# mrShark_Debugger.net
KiCad netlist of a schematic drawn in EAGLE
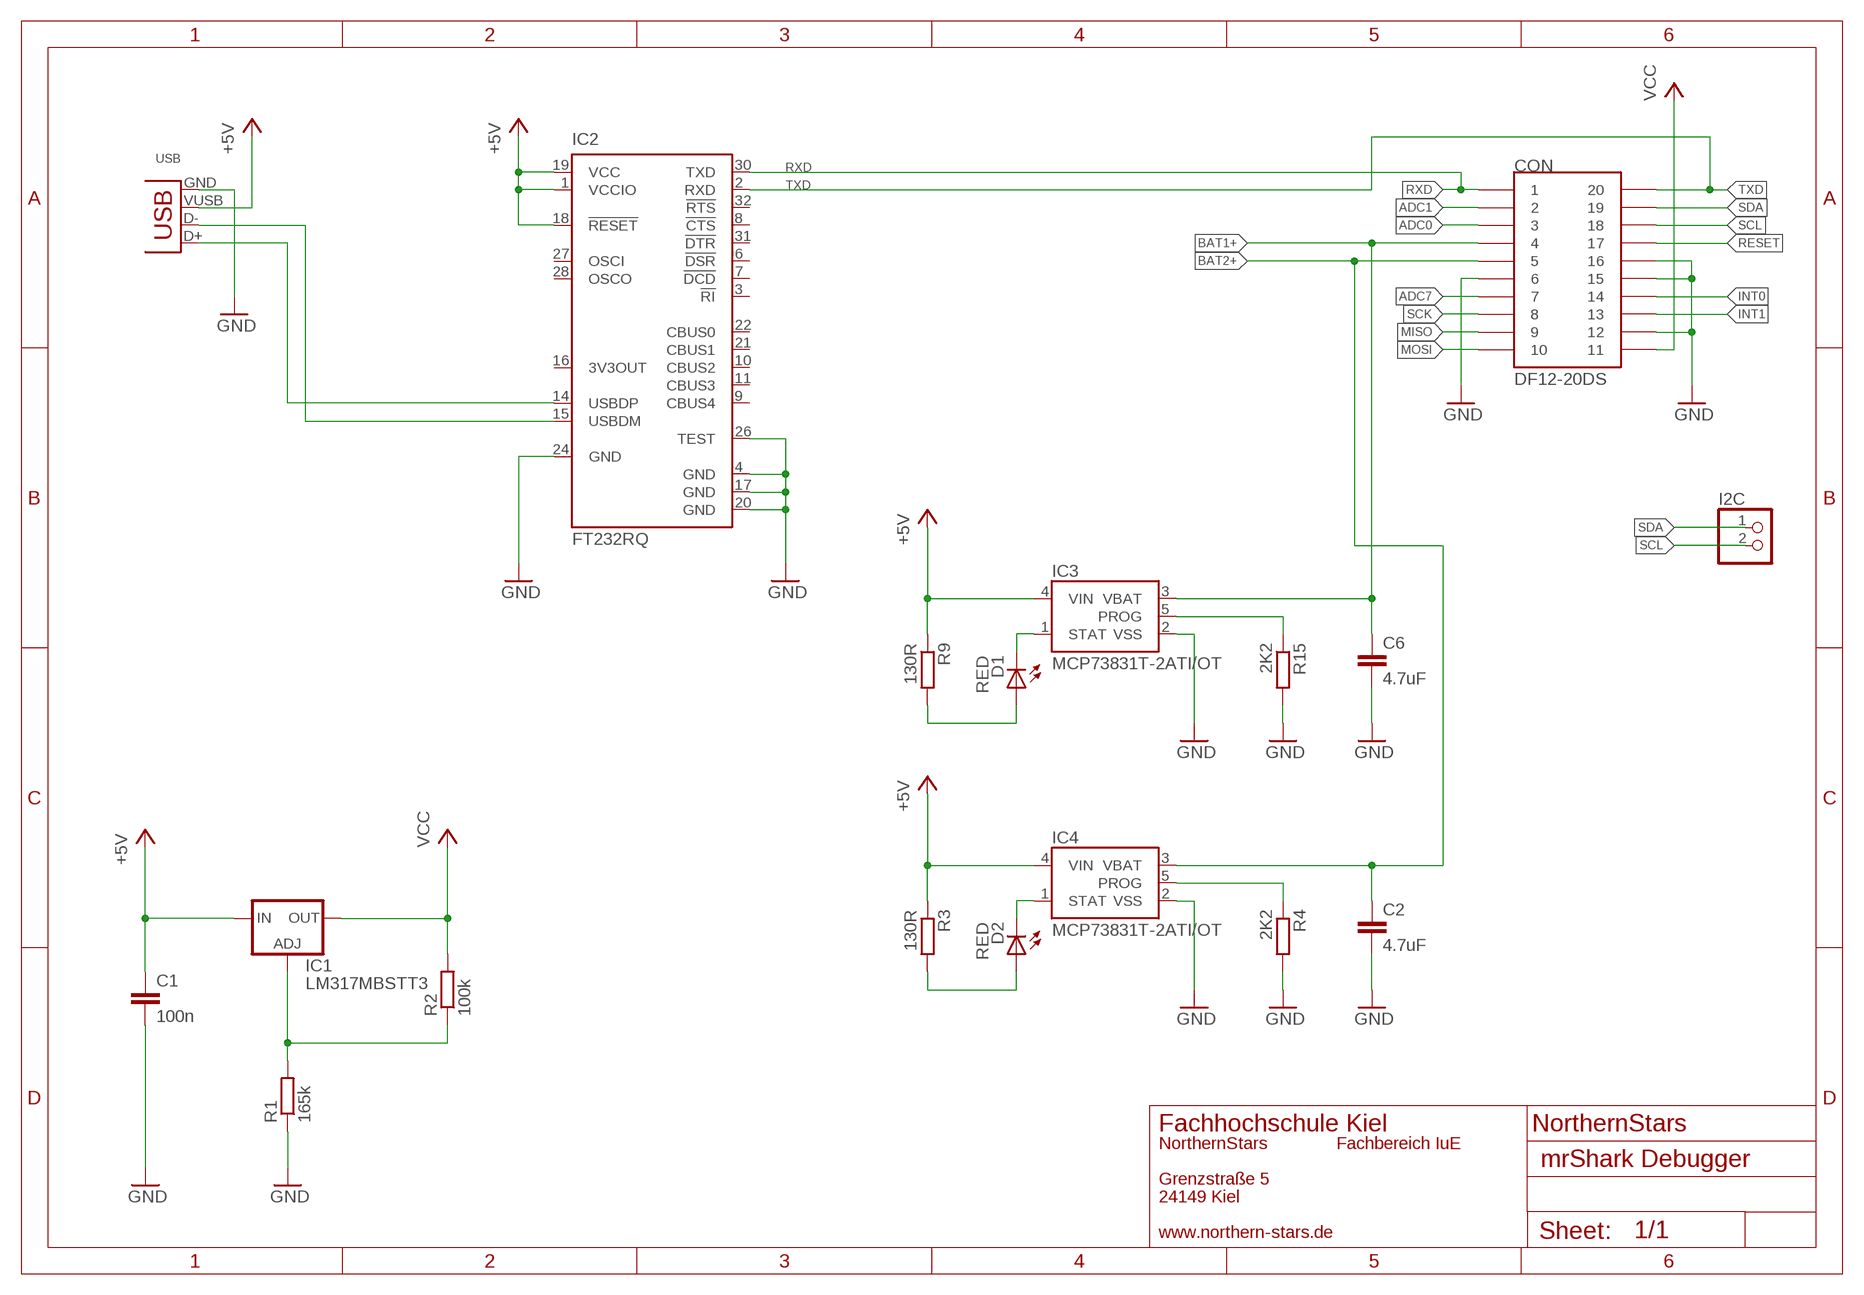
[diagram p0: schematic, sheet 1]

(export (version "E")
  (design (tool "Eeschema 10.0.6"))
  (components
    (comp (ref "C1")
      (value "100n")
      (footprint "eagle-import:C0201")
      (libsource (lib "eagle-import") (part "C-EUC0201"))
    )
    (comp (ref "C2")
      (value "4.7uF")
      (footprint "eagle-import:C0805")
      (libsource (lib "eagle-import") (part "C-EUC0805"))
    )
    (comp (ref "C6")
      (value "4.7uF")
      (footprint "eagle-import:C0805")
      (libsource (lib "eagle-import") (part "C-EUC0805"))
    )
    (comp (ref "CON")
      (value "DF12-20DS")
      (footprint "eagle-import:DF12-20DS")
      (libsource (lib "eagle-import") (part "DF12-20DS"))
    )
    (comp (ref "D1")
      (value "RED")
      (footprint "eagle-import:CHIP-LED0603")
      (libsource (lib "eagle-import") (part "LEDCHIP-LED0603"))
    )
    (comp (ref "D2")
      (value "RED")
      (footprint "eagle-import:CHIP-LED0603")
      (libsource (lib "eagle-import") (part "LEDCHIP-LED0603"))
    )
    (comp (ref "I2C")
      (value "PINHD-1X02_2.54-SMD")
      (footprint "eagle-import:1X02SMD")
      (libsource (lib "eagle-import") (part "PINHD-1X02_2.54-SMD"))
    )
    (comp (ref "IC1")
      (value "LM317MBSTT3")
      (footprint "eagle-import:SOT223")
      (libsource (lib "eagle-import") (part "LM317?MBSTT3"))
    )
    (comp (ref "IC2")
      (value "FT232RQ")
      (footprint "eagle-import:QFN32")
      (libsource (lib "eagle-import") (part "FT232RQ"))
    )
    (comp (ref "IC3")
      (value "MCP73831T-2ATI/OT")
      (footprint "eagle-import:SOT23-5")
      (libsource (lib "eagle-import") (part "MCP73831"))
    )
    (comp (ref "IC4")
      (value "MCP73831T-2ATI/OT")
      (footprint "eagle-import:SOT23-5")
      (libsource (lib "eagle-import") (part "MCP73831"))
    )
    (comp (ref "R1")
      (value "165k")
      (footprint "eagle-import:R0201")
      (libsource (lib "eagle-import") (part "R-EU_R0201"))
    )
    (comp (ref "R2")
      (value "100k")
      (footprint "eagle-import:R0201")
      (libsource (lib "eagle-import") (part "R-EU_R0201"))
    )
    (comp (ref "R3")
      (value "130R")
      (footprint "eagle-import:R0201")
      (libsource (lib "eagle-import") (part "R-EU_R0201"))
    )
    (comp (ref "R4")
      (value "2K2")
      (footprint "eagle-import:R0201")
      (libsource (lib "eagle-import") (part "R-EU_R0201"))
    )
    (comp (ref "R9")
      (value "130R")
      (footprint "eagle-import:R0201")
      (libsource (lib "eagle-import") (part "R-EU_R0201"))
    )
    (comp (ref "R15")
      (value "2K2")
      (footprint "eagle-import:R0201")
      (libsource (lib "eagle-import") (part "R-EU_R0201"))
    )
    (comp (ref "USB")
      (value "USB-B-S")
      (footprint "eagle-import:USB-B-SMT")
      (libsource (lib "eagle-import") (part "USB-B-S"))
    )
  )
  (nets
    (net (code "1") (name "+5V") (class "Default")
      (node (ref "C1") (pin "1") (pinfunction "1_1") (pintype "passive"))
      (node (ref "IC1") (pin "3") (pinfunction "IN_3") (pintype "input"))
      (node (ref "IC2") (pin "1") (pinfunction "VCCIO_1") (pintype "power_in"))
      (node (ref "IC2") (pin "18") (pinfunction "~{RESET}_18") (pintype "input"))
      (node (ref "IC2") (pin "19") (pinfunction "VCC_19") (pintype "power_in"))
      (node (ref "IC3") (pin "4") (pinfunction "VIN_4") (pintype "power_in"))
      (node (ref "IC4") (pin "4") (pinfunction "VIN_4") (pintype "power_in"))
      (node (ref "R3") (pin "1") (pinfunction "1_1") (pintype "passive"))
      (node (ref "R9") (pin "1") (pinfunction "1_1") (pintype "passive"))
      (node (ref "USB") (pin "VUSB") (pinfunction "VBUS_VUSB") (pintype "bidirectional"))
    )
    (net (code "2") (name "ADC0") (class "Default")
      (node (ref "CON") (pin "3") (pinfunction "3_3") (pintype "bidirectional"))
    )
    (net (code "3") (name "ADC1") (class "Default")
      (node (ref "CON") (pin "2") (pinfunction "2_2") (pintype "bidirectional"))
    )
    (net (code "4") (name "ADC7") (class "Default")
      (node (ref "CON") (pin "7") (pinfunction "7_7") (pintype "bidirectional"))
    )
    (net (code "5") (name "BAT1+") (class "Default")
      (node (ref "C6") (pin "1") (pinfunction "1_1") (pintype "passive"))
      (node (ref "CON") (pin "4") (pinfunction "4_4") (pintype "bidirectional"))
      (node (ref "IC3") (pin "3") (pinfunction "VBAT_3") (pintype "power_in"))
    )
    (net (code "6") (name "BAT2+") (class "Default")
      (node (ref "C2") (pin "1") (pinfunction "1_1") (pintype "passive"))
      (node (ref "CON") (pin "5") (pinfunction "5_5") (pintype "bidirectional"))
      (node (ref "IC4") (pin "3") (pinfunction "VBAT_3") (pintype "power_in"))
    )
    (net (code "7") (name "GND") (class "Default")
      (node (ref "C1") (pin "2") (pinfunction "2_2") (pintype "passive"))
      (node (ref "C2") (pin "2") (pinfunction "2_2") (pintype "passive"))
      (node (ref "C6") (pin "2") (pinfunction "2_2") (pintype "passive"))
      (node (ref "CON") (pin "12") (pinfunction "12_12") (pintype "bidirectional"))
      (node (ref "CON") (pin "15") (pinfunction "15_15") (pintype "bidirectional"))
      (node (ref "CON") (pin "16") (pinfunction "16_16") (pintype "bidirectional"))
      (node (ref "CON") (pin "6") (pinfunction "6_6") (pintype "bidirectional"))
      (node (ref "IC2") (pin "17") (pinfunction "GND_17") (pintype "power_in"))
      (node (ref "IC2") (pin "20") (pinfunction "GND_20") (pintype "power_in"))
      (node (ref "IC2") (pin "24") (pinfunction "GND_24") (pintype "power_in"))
      (node (ref "IC2") (pin "26") (pinfunction "TEST_26") (pintype "input"))
      (node (ref "IC2") (pin "4") (pinfunction "GND_4") (pintype "power_in"))
      (node (ref "IC3") (pin "2") (pinfunction "VSS_2") (pintype "power_in"))
      (node (ref "IC4") (pin "2") (pinfunction "VSS_2") (pintype "power_in"))
      (node (ref "R1") (pin "1") (pinfunction "1_1") (pintype "passive"))
      (node (ref "R15") (pin "2") (pinfunction "2_2") (pintype "passive"))
      (node (ref "R4") (pin "2") (pinfunction "2_2") (pintype "passive"))
      (node (ref "USB") (pin "GND") (pinfunction "GND_GND") (pintype "bidirectional"))
    )
    (net (code "8") (name "INT0") (class "Default")
      (node (ref "CON") (pin "14") (pinfunction "14_14") (pintype "bidirectional"))
    )
    (net (code "9") (name "INT1") (class "Default")
      (node (ref "CON") (pin "13") (pinfunction "13_13") (pintype "bidirectional"))
    )
    (net (code "10") (name "MISO") (class "Default")
      (node (ref "CON") (pin "9") (pinfunction "9_9") (pintype "bidirectional"))
    )
    (net (code "11") (name "MOSI") (class "Default")
      (node (ref "CON") (pin "10") (pinfunction "10_10") (pintype "bidirectional"))
    )
    (net (code "12") (name "Net-(D1-PadA)") (class "Default")
      (node (ref "D1") (pin "A") (pinfunction "A_A") (pintype "passive"))
      (node (ref "R9") (pin "2") (pinfunction "2_2") (pintype "passive"))
    )
    (net (code "13") (name "Net-(D2-PadA)") (class "Default")
      (node (ref "D2") (pin "A") (pinfunction "A_A") (pintype "passive"))
      (node (ref "R3") (pin "2") (pinfunction "2_2") (pintype "passive"))
    )
    (net (code "14") (name "Net-(IC1-ADJ)") (class "Default")
      (node (ref "IC1") (pin "1") (pinfunction "ADJ_1") (pintype "input"))
      (node (ref "R1") (pin "2") (pinfunction "2_2") (pintype "passive"))
      (node (ref "R2") (pin "1") (pinfunction "1_1") (pintype "passive"))
    )
    (net (code "15") (name "Net-(IC2-USBDM)") (class "Default")
      (node (ref "IC2") (pin "15") (pinfunction "USBDM_15") (pintype "bidirectional"))
      (node (ref "USB") (pin "D-") (pinfunction "D-_D-") (pintype "bidirectional"))
    )
    (net (code "16") (name "Net-(IC2-USBDP)") (class "Default")
      (node (ref "IC2") (pin "14") (pinfunction "USBDP_14") (pintype "bidirectional"))
      (node (ref "USB") (pin "D+") (pinfunction "D+_D+") (pintype "bidirectional"))
    )
    (net (code "17") (name "Net-(IC3-PROG)") (class "Default")
      (node (ref "IC3") (pin "5") (pinfunction "PROG_5") (pintype "input"))
      (node (ref "R15") (pin "1") (pinfunction "1_1") (pintype "passive"))
    )
    (net (code "18") (name "Net-(IC3-STAT)") (class "Default")
      (node (ref "D1") (pin "C") (pinfunction "C_C") (pintype "passive"))
      (node (ref "IC3") (pin "1") (pinfunction "STAT_1") (pintype "output"))
    )
    (net (code "19") (name "Net-(IC4-PROG)") (class "Default")
      (node (ref "IC4") (pin "5") (pinfunction "PROG_5") (pintype "input"))
      (node (ref "R4") (pin "1") (pinfunction "1_1") (pintype "passive"))
    )
    (net (code "20") (name "Net-(IC4-STAT)") (class "Default")
      (node (ref "D2") (pin "C") (pinfunction "C_C") (pintype "passive"))
      (node (ref "IC4") (pin "1") (pinfunction "STAT_1") (pintype "output"))
    )
    (net (code "21") (name "RESET") (class "Default")
      (node (ref "CON") (pin "17") (pinfunction "17_17") (pintype "bidirectional"))
    )
    (net (code "22") (name "RXD") (class "Default")
      (node (ref "CON") (pin "1") (pinfunction "1_1") (pintype "bidirectional"))
      (node (ref "IC2") (pin "30") (pinfunction "TXD_30") (pintype "output"))
    )
    (net (code "23") (name "SCK") (class "Default")
      (node (ref "CON") (pin "8") (pinfunction "8_8") (pintype "bidirectional"))
    )
    (net (code "24") (name "SCL") (class "Default")
      (node (ref "CON") (pin "18") (pinfunction "18_18") (pintype "bidirectional"))
      (node (ref "I2C") (pin "2") (pinfunction "2_2") (pintype "passive"))
    )
    (net (code "25") (name "SDA") (class "Default")
      (node (ref "CON") (pin "19") (pinfunction "19_19") (pintype "bidirectional"))
      (node (ref "I2C") (pin "1") (pinfunction "1_1") (pintype "passive"))
    )
    (net (code "26") (name "TXD") (class "Default")
      (node (ref "CON") (pin "20") (pinfunction "20_20") (pintype "bidirectional"))
      (node (ref "IC2") (pin "2") (pinfunction "RXD_2") (pintype "input"))
    )
    (net (code "27") (name "VCC") (class "Default")
      (node (ref "CON") (pin "11") (pinfunction "11_11") (pintype "bidirectional"))
      (node (ref "IC1") (pin "4") (pinfunction "OUT_4") (pintype "passive"))
      (node (ref "R2") (pin "2") (pinfunction "2_2") (pintype "passive"))
    )
    (net (code "28") (name "unconnected-(IC2-3V3OUT-Pad16)") (class "Default")
      (node (ref "IC2") (pin "16") (pinfunction "3V3OUT_16") (pintype "output"))
    )
    (net (code "29") (name "unconnected-(IC2-CBUS0-Pad22)") (class "Default")
      (node (ref "IC2") (pin "22") (pinfunction "CBUS0_22") (pintype "bidirectional"))
    )
    (net (code "30") (name "unconnected-(IC2-CBUS1-Pad21)") (class "Default")
      (node (ref "IC2") (pin "21") (pinfunction "CBUS1_21") (pintype "bidirectional"))
    )
    (net (code "31") (name "unconnected-(IC2-CBUS2-Pad10)") (class "Default")
      (node (ref "IC2") (pin "10") (pinfunction "CBUS2_10") (pintype "bidirectional"))
    )
    (net (code "32") (name "unconnected-(IC2-CBUS3-Pad11)") (class "Default")
      (node (ref "IC2") (pin "11") (pinfunction "CBUS3_11") (pintype "bidirectional"))
    )
    (net (code "33") (name "unconnected-(IC2-CBUS4-Pad9)") (class "Default")
      (node (ref "IC2") (pin "9") (pinfunction "CBUS4_9") (pintype "bidirectional"))
    )
    (net (code "34") (name "unconnected-(IC2-OSCI-Pad27)") (class "Default")
      (node (ref "IC2") (pin "27") (pinfunction "OSCI_27") (pintype "input"))
    )
    (net (code "35") (name "unconnected-(IC2-OSCO-Pad28)") (class "Default")
      (node (ref "IC2") (pin "28") (pinfunction "OSCO_28") (pintype "output"))
    )
    (net (code "36") (name "unconnected-(IC2-~{CTS}-Pad8)") (class "Default")
      (node (ref "IC2") (pin "8") (pinfunction "~{CTS}_8") (pintype "input"))
    )
    (net (code "37") (name "unconnected-(IC2-~{DCD}-Pad7)") (class "Default")
      (node (ref "IC2") (pin "7") (pinfunction "~{DCD}_7") (pintype "input"))
    )
    (net (code "38") (name "unconnected-(IC2-~{DSR}-Pad6)") (class "Default")
      (node (ref "IC2") (pin "6") (pinfunction "~{DSR}_6") (pintype "input"))
    )
    (net (code "39") (name "unconnected-(IC2-~{DTR}-Pad31)") (class "Default")
      (node (ref "IC2") (pin "31") (pinfunction "~{DTR}_31") (pintype "output"))
    )
    (net (code "40") (name "unconnected-(IC2-~{RI}-Pad3)") (class "Default")
      (node (ref "IC2") (pin "3") (pinfunction "~{RI}_3") (pintype "input"))
    )
    (net (code "41") (name "unconnected-(IC2-~{RTS}-Pad32)") (class "Default")
      (node (ref "IC2") (pin "32") (pinfunction "~{RTS}_32") (pintype "output"))
    )
  )
)
